# air_node.net
KiCad netlist of a schematic drawn in EAGLE
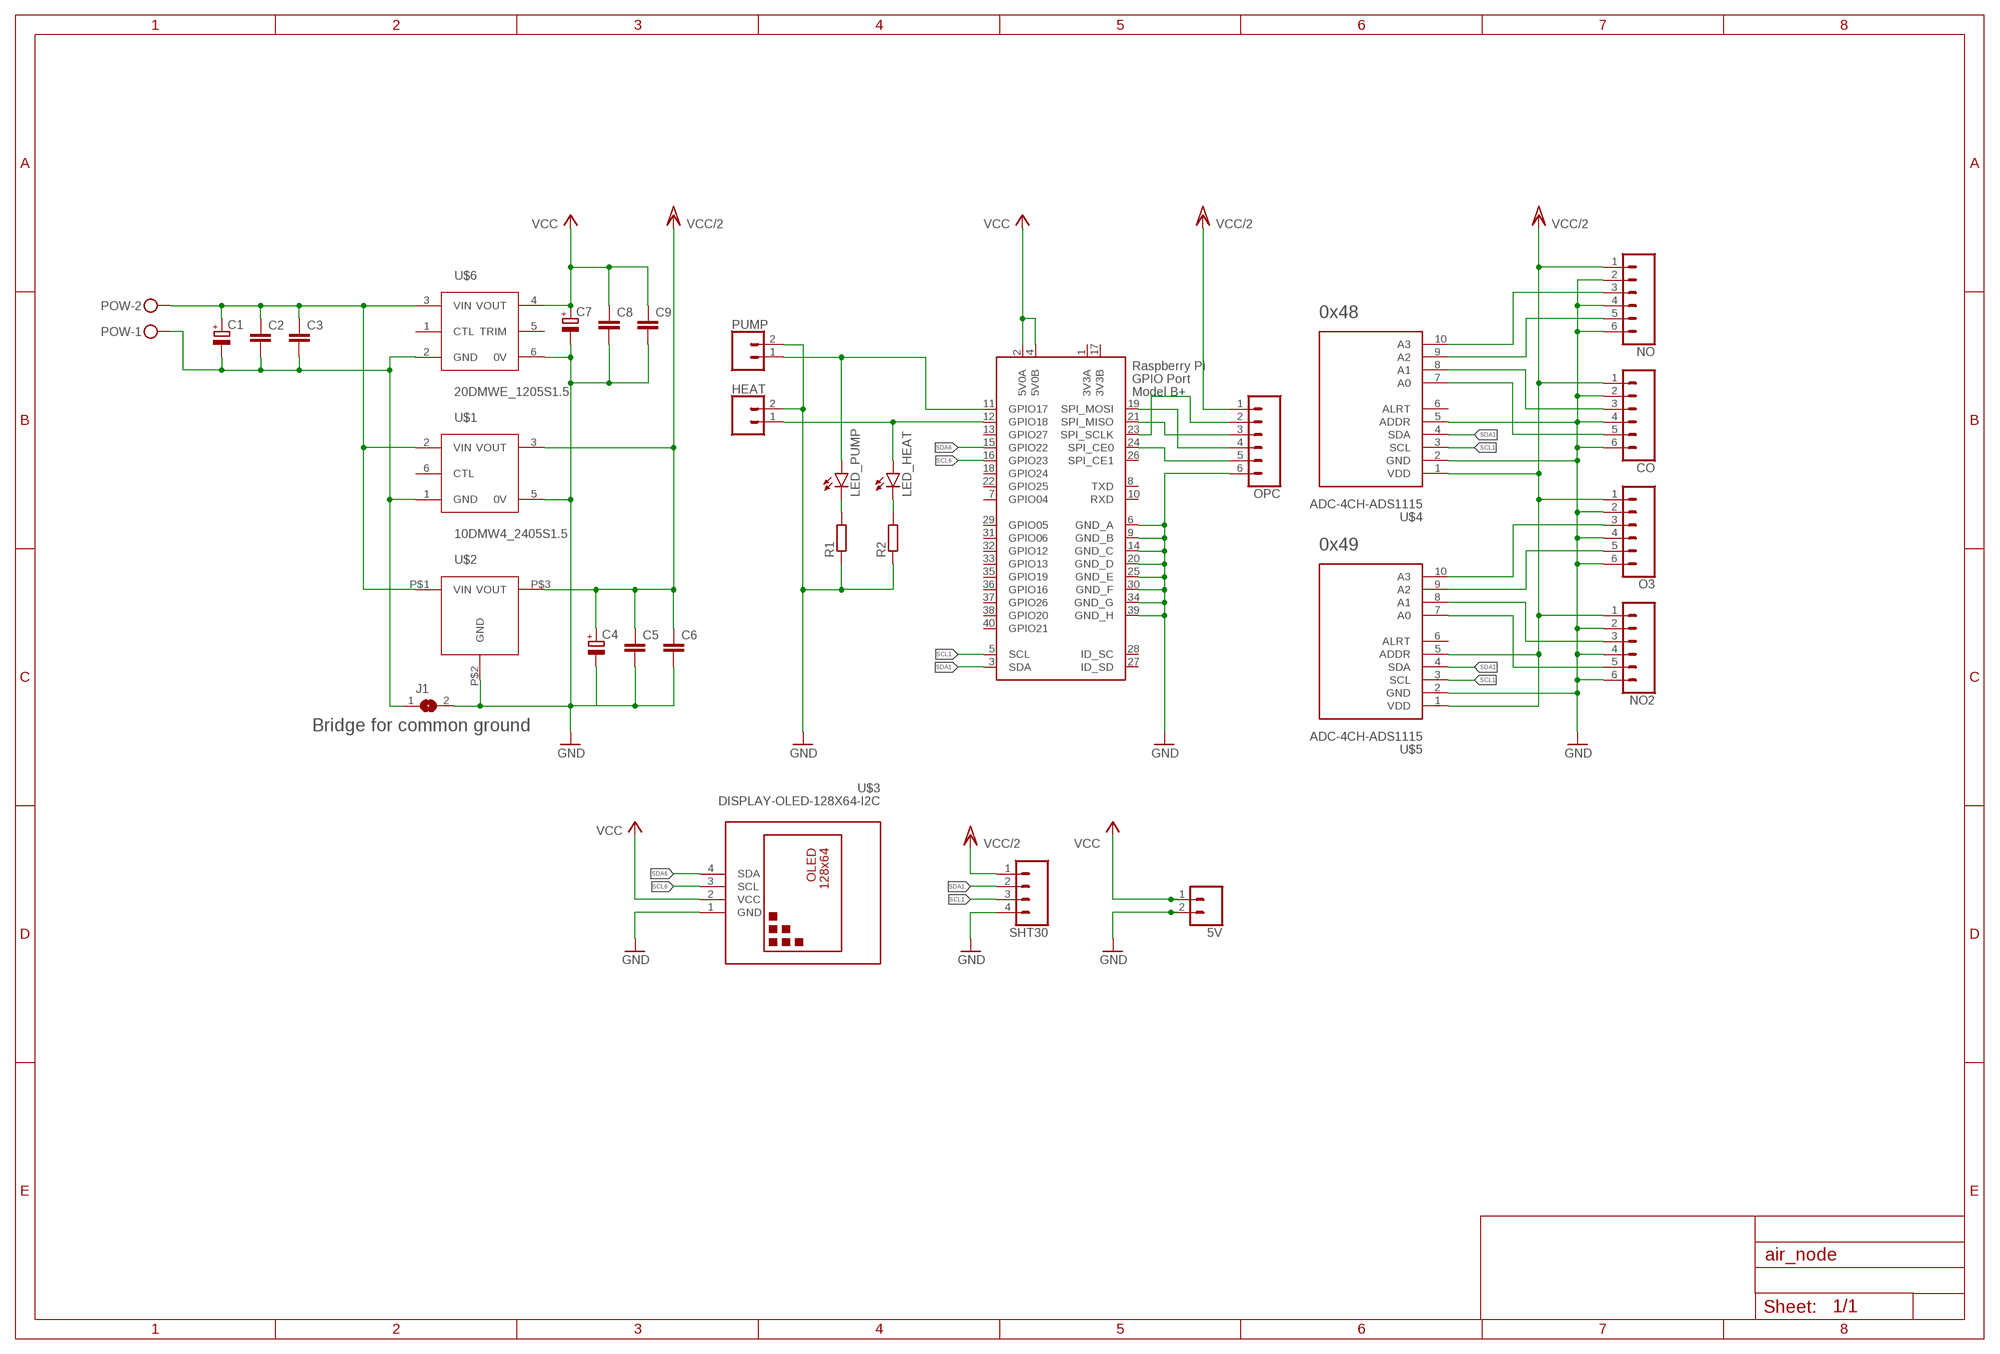
[diagram p0: schematic, sheet 1]

(export (version "E")
  (design (tool "Eeschema 10.0.6"))
  (components
    (comp (ref "5V")
      (value "CONN_021X02_NO_SILK")
      (footprint "eagle-import:1X02_NO_SILK")
      (libsource (lib "eagle-import") (part "CONN_021X02_NO_SILK"))
    )
    (comp (ref "C1")
      (value "CPOL-EUE3.5-10")
      (footprint "eagle-import:E3,5-10")
      (libsource (lib "eagle-import") (part "CPOL-EUE3.5-10"))
    )
    (comp (ref "C2")
      (value "C-EUC1206")
      (footprint "eagle-import:C1206")
      (libsource (lib "eagle-import") (part "C-EUC1206"))
    )
    (comp (ref "C3")
      (value "C-EUC0805")
      (footprint "eagle-import:C0805")
      (libsource (lib "eagle-import") (part "C-EUC0805"))
    )
    (comp (ref "C4")
      (value "CPOL-EUE3.5-10")
      (footprint "eagle-import:E3,5-10")
      (libsource (lib "eagle-import") (part "CPOL-EUE3.5-10"))
    )
    (comp (ref "C5")
      (value "C-EUC1206")
      (footprint "eagle-import:C1206")
      (libsource (lib "eagle-import") (part "C-EUC1206"))
    )
    (comp (ref "C6")
      (value "C-EUC0805")
      (footprint "eagle-import:C0805")
      (libsource (lib "eagle-import") (part "C-EUC0805"))
    )
    (comp (ref "C7")
      (value "CPOL-EUE3.5-10")
      (footprint "eagle-import:E3,5-10")
      (libsource (lib "eagle-import") (part "CPOL-EUE3.5-10"))
    )
    (comp (ref "C8")
      (value "C-EUC1206")
      (footprint "eagle-import:C1206")
      (libsource (lib "eagle-import") (part "C-EUC1206"))
    )
    (comp (ref "C9")
      (value "C-EUC0805")
      (footprint "eagle-import:C0805")
      (libsource (lib "eagle-import") (part "C-EUC0805"))
    )
    (comp (ref "CO")
      (value "CONN_06NO_SILK_FEMALE_PTH")
      (footprint "eagle-import:1X06_NO_SILK")
      (libsource (lib "eagle-import") (part "CONN_06NO_SILK_FEMALE_PTH"))
    )
    (comp (ref "HEAT")
      (value "CONN_021X02_NO_SILK")
      (footprint "eagle-import:1X02_NO_SILK")
      (libsource (lib "eagle-import") (part "CONN_021X02_NO_SILK"))
    )
    (comp (ref "J1") (value "SJ") (footprint "eagle-import:SJ") (libsource (lib "eagle-import") (part "SJ")))
    (comp (ref "LED_HEAT")
      (value "LEDCHIP-LED0805")
      (footprint "eagle-import:CHIP-LED0805")
      (libsource (lib "eagle-import") (part "LEDCHIP-LED0805"))
    )
    (comp (ref "LED_PUMP")
      (value "LEDCHIP-LED0805")
      (footprint "eagle-import:CHIP-LED0805")
      (libsource (lib "eagle-import") (part "LEDCHIP-LED0805"))
    )
    (comp (ref "NO")
      (value "CONN_06NO_SILK_FEMALE_PTH")
      (footprint "eagle-import:1X06_NO_SILK")
      (libsource (lib "eagle-import") (part "CONN_06NO_SILK_FEMALE_PTH"))
    )
    (comp (ref "NO2")
      (value "CONN_06NO_SILK_FEMALE_PTH")
      (footprint "eagle-import:1X06_NO_SILK")
      (libsource (lib "eagle-import") (part "CONN_06NO_SILK_FEMALE_PTH"))
    )
    (comp (ref "O3")
      (value "CONN_06NO_SILK_FEMALE_PTH")
      (footprint "eagle-import:1X06_NO_SILK")
      (libsource (lib "eagle-import") (part "CONN_06NO_SILK_FEMALE_PTH"))
    )
    (comp (ref "OPC")
      (value "CONN_06NO_SILK_FEMALE_PTH")
      (footprint "eagle-import:1X06_NO_SILK")
      (fields (field (name "SPICEPREFIX") "X"))
      (libsource (lib "eagle-import") (part "CONN_06NO_SILK_FEMALE_PTH"))
    )
    (comp (ref "POW")
      (value "MKDSN1,5/2-5,08")
      (footprint "eagle-import:MKDSN1,5_2-5,08")
      (libsource (lib "eagle-import") (part "MKDSN1,5/2-5,08"))
    )
    (comp (ref "PUMP")
      (value "CONN_021X02_NO_SILK")
      (footprint "eagle-import:1X02_NO_SILK")
      (libsource (lib "eagle-import") (part "CONN_021X02_NO_SILK"))
    )
    (comp (ref "R1")
      (value "R-EU_R0805")
      (footprint "eagle-import:R0805")
      (libsource (lib "eagle-import") (part "R-EU_R0805"))
    )
    (comp (ref "R2")
      (value "R-EU_R0805")
      (footprint "eagle-import:R0805")
      (libsource (lib "eagle-import") (part "R-EU_R0805"))
    )
    (comp (ref "SHT30")
      (value "CONN_041X04_NO_SILK")
      (footprint "eagle-import:1X04_NO_SILK")
      (libsource (lib "eagle-import") (part "CONN_041X04_NO_SILK"))
    )
    (comp (ref "U$1")
      (value "10DMW4_2405S1.5")
      (footprint "eagle-import:10DMW4_2405S1.5")
      (libsource (lib "eagle-import") (part "10DMW4_2405S1.5"))
    )
    (comp (ref "U$2")
      (value "LME78_05-1.0")
      (footprint "eagle-import:LME78_05-1.0")
      (libsource (lib "eagle-import") (part "LME78_05-1.0"))
    )
    (comp (ref "U$3")
      (value "DISPLAY-OLED-128X64-I2C")
      (footprint "eagle-import:DISPLAY-OLED-128X64-I2C")
      (libsource (lib "eagle-import") (part "DISPLAY-OLED-128X64-I2C"))
    )
    (comp (ref "U$4")
      (value "ADC-4CH-ADS1115")
      (footprint "eagle-import:ADC-4CH-ADS1115")
      (libsource (lib "eagle-import") (part "ADC-4CH-ADS1115"))
    )
    (comp (ref "U$5")
      (value "ADC-4CH-ADS1115")
      (footprint "eagle-import:ADC-4CH-ADS1115")
      (libsource (lib "eagle-import") (part "ADC-4CH-ADS1115"))
    )
    (comp (ref "U$6")
      (value "20DMWE_1205S1.5")
      (footprint "eagle-import:20DMWE_1205S1.5")
      (libsource (lib "eagle-import") (part "20DMWE_1205S1.5"))
    )
    (comp (ref "X1")
      (value "RASPI_BOARD_B+#_E4")
      (footprint "eagle-import:RASPI_BOARD_B+_EDGES_4DRILL")
      (libsource (lib "eagle-import") (part "RASPI_BOARD_B+#_E4"))
    )
  )
  (nets
    (net (code "1") (name "/3V3A") (class "Default")
      (node (ref "X1") (pin "1") (pinfunction "3V3A_1") (pintype "power_in"))
    )
    (net (code "2") (name "/3V3B") (class "Default")
      (node (ref "X1") (pin "17") (pinfunction "3V3B_17") (pintype "power_in"))
    )
    (net (code "3") (name "GND") (class "Default")
      (node (ref "5V") (pin "2") (pinfunction "2_2") (pintype "passive"))
      (node (ref "C4") (pin "-") (pinfunction "-_-") (pintype "passive"))
      (node (ref "C5") (pin "2") (pinfunction "2_2") (pintype "passive"))
      (node (ref "C6") (pin "2") (pinfunction "2_2") (pintype "passive"))
      (node (ref "C7") (pin "-") (pinfunction "-_-") (pintype "passive"))
      (node (ref "C8") (pin "2") (pinfunction "2_2") (pintype "passive"))
      (node (ref "C9") (pin "2") (pinfunction "2_2") (pintype "passive"))
      (node (ref "CO") (pin "2") (pinfunction "2_2") (pintype "passive"))
      (node (ref "CO") (pin "4") (pinfunction "4_4") (pintype "passive"))
      (node (ref "CO") (pin "6") (pinfunction "6_6") (pintype "passive"))
      (node (ref "HEAT") (pin "2") (pinfunction "2_2") (pintype "passive"))
      (node (ref "J1") (pin "2") (pinfunction "2_2") (pintype "passive"))
      (node (ref "NO") (pin "2") (pinfunction "2_2") (pintype "passive"))
      (node (ref "NO") (pin "4") (pinfunction "4_4") (pintype "passive"))
      (node (ref "NO") (pin "6") (pinfunction "6_6") (pintype "passive"))
      (node (ref "NO2") (pin "2") (pinfunction "2_2") (pintype "passive"))
      (node (ref "NO2") (pin "4") (pinfunction "4_4") (pintype "passive"))
      (node (ref "NO2") (pin "6") (pinfunction "6_6") (pintype "passive"))
      (node (ref "O3") (pin "2") (pinfunction "2_2") (pintype "passive"))
      (node (ref "O3") (pin "4") (pinfunction "4_4") (pintype "passive"))
      (node (ref "O3") (pin "6") (pinfunction "6_6") (pintype "passive"))
      (node (ref "OPC") (pin "6") (pinfunction "6_6") (pintype "passive"))
      (node (ref "PUMP") (pin "2") (pinfunction "2_2") (pintype "passive"))
      (node (ref "R1") (pin "1") (pinfunction "1_1") (pintype "passive"))
      (node (ref "R2") (pin "1") (pinfunction "1_1") (pintype "passive"))
      (node (ref "SHT30") (pin "4") (pinfunction "4_4") (pintype "passive"))
      (node (ref "U$1") (pin "5") (pinfunction "0V_5") (pintype "bidirectional"))
      (node (ref "U$2") (pin "P$2") (pinfunction "GND_P$2") (pintype "bidirectional"))
      (node (ref "U$3") (pin "1") (pinfunction "GND_1") (pintype "power_in"))
      (node (ref "U$4") (pin "2") (pinfunction "GND_2") (pintype "power_in"))
      (node (ref "U$4") (pin "5") (pinfunction "ADDR_5") (pintype "bidirectional"))
      (node (ref "U$5") (pin "2") (pinfunction "GND_2") (pintype "power_in"))
      (node (ref "U$6") (pin "6") (pinfunction "0V_6") (pintype "bidirectional"))
      (node (ref "X1") (pin "14") (pinfunction "GND_C_14") (pintype "power_in"))
      (node (ref "X1") (pin "20") (pinfunction "GND_D_20") (pintype "power_in"))
      (node (ref "X1") (pin "25") (pinfunction "GND_E_25") (pintype "power_in"))
      (node (ref "X1") (pin "30") (pinfunction "GND_F_30") (pintype "power_in"))
      (node (ref "X1") (pin "34") (pinfunction "GND_G_34") (pintype "power_in"))
      (node (ref "X1") (pin "39") (pinfunction "GND_H_39") (pintype "power_in"))
      (node (ref "X1") (pin "6") (pinfunction "GND_A_6") (pintype "power_in"))
      (node (ref "X1") (pin "9") (pinfunction "GND_B_9") (pintype "power_in"))
    )
    (net (code "4") (name "Net-(LED_HEAT-PadC)") (class "Default")
      (node (ref "LED_HEAT") (pin "C") (pinfunction "C_C") (pintype "passive"))
      (node (ref "R2") (pin "2") (pinfunction "2_2") (pintype "passive"))
    )
    (net (code "5") (name "Net-(LED_PUMP-PadC)") (class "Default")
      (node (ref "LED_PUMP") (pin "C") (pinfunction "C_C") (pintype "passive"))
      (node (ref "R1") (pin "2") (pinfunction "2_2") (pintype "passive"))
    )
    (net (code "6") (name "Net-(POWA-KL)") (class "Default")
      (node (ref "C1") (pin "-") (pinfunction "-_-") (pintype "passive"))
      (node (ref "C2") (pin "2") (pinfunction "2_2") (pintype "passive"))
      (node (ref "C3") (pin "2") (pinfunction "2_2") (pintype "passive"))
      (node (ref "J1") (pin "1") (pinfunction "1_1") (pintype "passive"))
      (node (ref "POW") (pin "1") (pinfunction "KL_1") (pintype "passive"))
      (node (ref "U$1") (pin "1") (pinfunction "GND_1") (pintype "bidirectional"))
      (node (ref "U$6") (pin "2") (pinfunction "GND_2") (pintype "bidirectional"))
    )
    (net (code "7") (name "Net-(POWB-KL)") (class "Default")
      (node (ref "C1") (pin "+") (pinfunction "+_+") (pintype "passive"))
      (node (ref "C2") (pin "1") (pinfunction "1_1") (pintype "passive"))
      (node (ref "C3") (pin "1") (pinfunction "1_1") (pintype "passive"))
      (node (ref "POW") (pin "2") (pinfunction "KL_2") (pintype "passive"))
      (node (ref "U$1") (pin "2") (pinfunction "VIN_2") (pintype "bidirectional"))
      (node (ref "U$2") (pin "P$1") (pinfunction "VIN_P$1") (pintype "bidirectional"))
      (node (ref "U$6") (pin "3") (pinfunction "VIN_3") (pintype "bidirectional"))
    )
    (net (code "8") (name "Net-(U$4-A0)") (class "Default")
      (node (ref "CO") (pin "5") (pinfunction "5_5") (pintype "passive"))
      (node (ref "U$4") (pin "7") (pinfunction "A0_7") (pintype "input"))
    )
    (net (code "9") (name "Net-(U$4-A1)") (class "Default")
      (node (ref "CO") (pin "3") (pinfunction "3_3") (pintype "passive"))
      (node (ref "U$4") (pin "8") (pinfunction "A1_8") (pintype "input"))
    )
    (net (code "10") (name "Net-(U$4-A2)") (class "Default")
      (node (ref "NO") (pin "5") (pinfunction "5_5") (pintype "passive"))
      (node (ref "U$4") (pin "9") (pinfunction "A2_9") (pintype "input"))
    )
    (net (code "11") (name "Net-(U$4-A3)") (class "Default")
      (node (ref "NO") (pin "3") (pinfunction "3_3") (pintype "passive"))
      (node (ref "U$4") (pin "10") (pinfunction "A3_10") (pintype "input"))
    )
    (net (code "12") (name "Net-(U$5-A0)") (class "Default")
      (node (ref "NO2") (pin "5") (pinfunction "5_5") (pintype "passive"))
      (node (ref "U$5") (pin "7") (pinfunction "A0_7") (pintype "input"))
    )
    (net (code "13") (name "Net-(U$5-A1)") (class "Default")
      (node (ref "NO2") (pin "3") (pinfunction "3_3") (pintype "passive"))
      (node (ref "U$5") (pin "8") (pinfunction "A1_8") (pintype "input"))
    )
    (net (code "14") (name "Net-(U$5-A2)") (class "Default")
      (node (ref "O3") (pin "5") (pinfunction "5_5") (pintype "passive"))
      (node (ref "U$5") (pin "9") (pinfunction "A2_9") (pintype "input"))
    )
    (net (code "15") (name "Net-(U$5-A3)") (class "Default")
      (node (ref "O3") (pin "3") (pinfunction "3_3") (pintype "passive"))
      (node (ref "U$5") (pin "10") (pinfunction "A3_10") (pintype "input"))
    )
    (net (code "16") (name "Net-(X1-GPIO17)") (class "Default")
      (node (ref "LED_PUMP") (pin "A") (pinfunction "A_A") (pintype "passive"))
      (node (ref "PUMP") (pin "1") (pinfunction "1_1") (pintype "passive"))
      (node (ref "X1") (pin "11") (pinfunction "GPIO17_11") (pintype "bidirectional"))
    )
    (net (code "17") (name "Net-(X1-GPIO18)") (class "Default")
      (node (ref "HEAT") (pin "1") (pinfunction "1_1") (pintype "passive"))
      (node (ref "LED_HEAT") (pin "A") (pinfunction "A_A") (pintype "passive"))
      (node (ref "X1") (pin "12") (pinfunction "GPIO18_12") (pintype "bidirectional"))
    )
    (net (code "18") (name "Net-(X1-SPI_CE0)") (class "Default")
      (node (ref "OPC") (pin "5") (pinfunction "5_5") (pintype "passive"))
      (node (ref "X1") (pin "24") (pinfunction "SPI_CE0_24") (pintype "bidirectional"))
    )
    (net (code "19") (name "Net-(X1-SPI_MISO)") (class "Default")
      (node (ref "OPC") (pin "3") (pinfunction "3_3") (pintype "passive"))
      (node (ref "X1") (pin "21") (pinfunction "SPI_MISO_21") (pintype "bidirectional"))
    )
    (net (code "20") (name "Net-(X1-SPI_MOSI)") (class "Default")
      (node (ref "OPC") (pin "4") (pinfunction "4_4") (pintype "passive"))
      (node (ref "X1") (pin "19") (pinfunction "SPI_MOSI_19") (pintype "bidirectional"))
    )
    (net (code "21") (name "Net-(X1-SPI_SCLK)") (class "Default")
      (node (ref "OPC") (pin "2") (pinfunction "2_2") (pintype "passive"))
      (node (ref "X1") (pin "23") (pinfunction "SPI_SCLK_23") (pintype "bidirectional"))
    )
    (net (code "22") (name "SCL1") (class "Default")
      (node (ref "SHT30") (pin "3") (pinfunction "3_3") (pintype "passive"))
      (node (ref "U$4") (pin "3") (pinfunction "SCL_3") (pintype "bidirectional"))
      (node (ref "U$5") (pin "3") (pinfunction "SCL_3") (pintype "bidirectional"))
      (node (ref "X1") (pin "5") (pinfunction "SCL_5") (pintype "bidirectional"))
    )
    (net (code "23") (name "SCL6") (class "Default")
      (node (ref "U$3") (pin "3") (pinfunction "SCL_3") (pintype "bidirectional"))
      (node (ref "X1") (pin "16") (pinfunction "GPIO23_16") (pintype "bidirectional"))
    )
    (net (code "24") (name "SDA1") (class "Default")
      (node (ref "SHT30") (pin "2") (pinfunction "2_2") (pintype "passive"))
      (node (ref "U$4") (pin "4") (pinfunction "SDA_4") (pintype "bidirectional"))
      (node (ref "U$5") (pin "4") (pinfunction "SDA_4") (pintype "bidirectional"))
      (node (ref "X1") (pin "3") (pinfunction "SDA_3") (pintype "bidirectional"))
    )
    (net (code "25") (name "SDA6") (class "Default")
      (node (ref "U$3") (pin "4") (pinfunction "SDA_4") (pintype "bidirectional"))
      (node (ref "X1") (pin "15") (pinfunction "GPIO22_15") (pintype "bidirectional"))
    )
    (net (code "26") (name "VCC") (class "Default")
      (node (ref "5V") (pin "1") (pinfunction "1_1") (pintype "passive"))
      (node (ref "C7") (pin "+") (pinfunction "+_+") (pintype "passive"))
      (node (ref "C8") (pin "1") (pinfunction "1_1") (pintype "passive"))
      (node (ref "C9") (pin "1") (pinfunction "1_1") (pintype "passive"))
      (node (ref "U$3") (pin "2") (pinfunction "VCC_2") (pintype "power_in"))
      (node (ref "U$6") (pin "4") (pinfunction "VOUT_4") (pintype "bidirectional"))
      (node (ref "X1") (pin "2") (pinfunction "5V0A_2") (pintype "power_in"))
      (node (ref "X1") (pin "4") (pinfunction "5V0B_4") (pintype "power_in"))
    )
    (net (code "27") (name "VCC{slash}2") (class "Default")
      (node (ref "C4") (pin "+") (pinfunction "+_+") (pintype "passive"))
      (node (ref "C5") (pin "1") (pinfunction "1_1") (pintype "passive"))
      (node (ref "C6") (pin "1") (pinfunction "1_1") (pintype "passive"))
      (node (ref "CO") (pin "1") (pinfunction "1_1") (pintype "passive"))
      (node (ref "NO") (pin "1") (pinfunction "1_1") (pintype "passive"))
      (node (ref "NO2") (pin "1") (pinfunction "1_1") (pintype "passive"))
      (node (ref "O3") (pin "1") (pinfunction "1_1") (pintype "passive"))
      (node (ref "OPC") (pin "1") (pinfunction "1_1") (pintype "passive"))
      (node (ref "SHT30") (pin "1") (pinfunction "1_1") (pintype "passive"))
      (node (ref "U$1") (pin "3") (pinfunction "VOUT_3") (pintype "bidirectional"))
      (node (ref "U$2") (pin "P$3") (pinfunction "VOUT_P$3") (pintype "bidirectional"))
      (node (ref "U$4") (pin "1") (pinfunction "VDD_1") (pintype "power_in"))
      (node (ref "U$5") (pin "1") (pinfunction "VDD_1") (pintype "power_in"))
      (node (ref "U$5") (pin "5") (pinfunction "ADDR_5") (pintype "bidirectional"))
    )
    (net (code "28") (name "unconnected-(U$1-CTL-Pad6)") (class "Default")
      (node (ref "U$1") (pin "6") (pinfunction "CTL_6") (pintype "bidirectional"))
    )
    (net (code "29") (name "unconnected-(U$4-ALRT-Pad6)") (class "Default")
      (node (ref "U$4") (pin "6") (pinfunction "ALRT_6") (pintype "bidirectional"))
    )
    (net (code "30") (name "unconnected-(U$5-ALRT-Pad6)") (class "Default")
      (node (ref "U$5") (pin "6") (pinfunction "ALRT_6") (pintype "bidirectional"))
    )
    (net (code "31") (name "unconnected-(U$6-CTL-Pad1)") (class "Default")
      (node (ref "U$6") (pin "1") (pinfunction "CTL_1") (pintype "bidirectional"))
    )
    (net (code "32") (name "unconnected-(U$6-TRIM-Pad5)") (class "Default")
      (node (ref "U$6") (pin "5") (pinfunction "TRIM_5") (pintype "bidirectional"))
    )
    (net (code "33") (name "unconnected-(X1-GPIO04-Pad7)") (class "Default")
      (node (ref "X1") (pin "7") (pinfunction "GPIO04_7") (pintype "bidirectional"))
    )
    (net (code "34") (name "unconnected-(X1-GPIO05-Pad29)") (class "Default")
      (node (ref "X1") (pin "29") (pinfunction "GPIO05_29") (pintype "no_connect"))
    )
    (net (code "35") (name "unconnected-(X1-GPIO06-Pad31)") (class "Default")
      (node (ref "X1") (pin "31") (pinfunction "GPIO06_31") (pintype "no_connect"))
    )
    (net (code "36") (name "unconnected-(X1-GPIO12-Pad32)") (class "Default")
      (node (ref "X1") (pin "32") (pinfunction "GPIO12_32") (pintype "no_connect"))
    )
    (net (code "37") (name "unconnected-(X1-GPIO13-Pad33)") (class "Default")
      (node (ref "X1") (pin "33") (pinfunction "GPIO13_33") (pintype "no_connect"))
    )
    (net (code "38") (name "unconnected-(X1-GPIO16-Pad36)") (class "Default")
      (node (ref "X1") (pin "36") (pinfunction "GPIO16_36") (pintype "no_connect"))
    )
    (net (code "39") (name "unconnected-(X1-GPIO19-Pad35)") (class "Default")
      (node (ref "X1") (pin "35") (pinfunction "GPIO19_35") (pintype "no_connect"))
    )
    (net (code "40") (name "unconnected-(X1-GPIO20-Pad38)") (class "Default")
      (node (ref "X1") (pin "38") (pinfunction "GPIO20_38") (pintype "no_connect"))
    )
    (net (code "41") (name "unconnected-(X1-GPIO21-Pad40)") (class "Default")
      (node (ref "X1") (pin "40") (pinfunction "GPIO21_40") (pintype "no_connect"))
    )
    (net (code "42") (name "unconnected-(X1-GPIO24-Pad18)") (class "Default")
      (node (ref "X1") (pin "18") (pinfunction "GPIO24_18") (pintype "bidirectional"))
    )
    (net (code "43") (name "unconnected-(X1-GPIO25-Pad22)") (class "Default")
      (node (ref "X1") (pin "22") (pinfunction "GPIO25_22") (pintype "bidirectional"))
    )
    (net (code "44") (name "unconnected-(X1-GPIO26-Pad37)") (class "Default")
      (node (ref "X1") (pin "37") (pinfunction "GPIO26_37") (pintype "no_connect"))
    )
    (net (code "45") (name "unconnected-(X1-GPIO27-Pad13)") (class "Default")
      (node (ref "X1") (pin "13") (pinfunction "GPIO27_13") (pintype "bidirectional"))
    )
    (net (code "46") (name "unconnected-(X1-ID_SC-Pad28)") (class "Default")
      (node (ref "X1") (pin "28") (pinfunction "ID_SC_28") (pintype "no_connect"))
    )
    (net (code "47") (name "unconnected-(X1-ID_SD-Pad27)") (class "Default")
      (node (ref "X1") (pin "27") (pinfunction "ID_SD_27") (pintype "no_connect"))
    )
    (net (code "48") (name "unconnected-(X1-RXD-Pad10)") (class "Default")
      (node (ref "X1") (pin "10") (pinfunction "RXD_10") (pintype "bidirectional"))
    )
    (net (code "49") (name "unconnected-(X1-SPI_CE1-Pad26)") (class "Default")
      (node (ref "X1") (pin "26") (pinfunction "SPI_CE1_26") (pintype "bidirectional"))
    )
    (net (code "50") (name "unconnected-(X1-TXD-Pad8)") (class "Default")
      (node (ref "X1") (pin "8") (pinfunction "TXD_8") (pintype "bidirectional"))
    )
  )
)
